# Output_dig2.net
KiCad netlist of a schematic drawn in Altium Designer
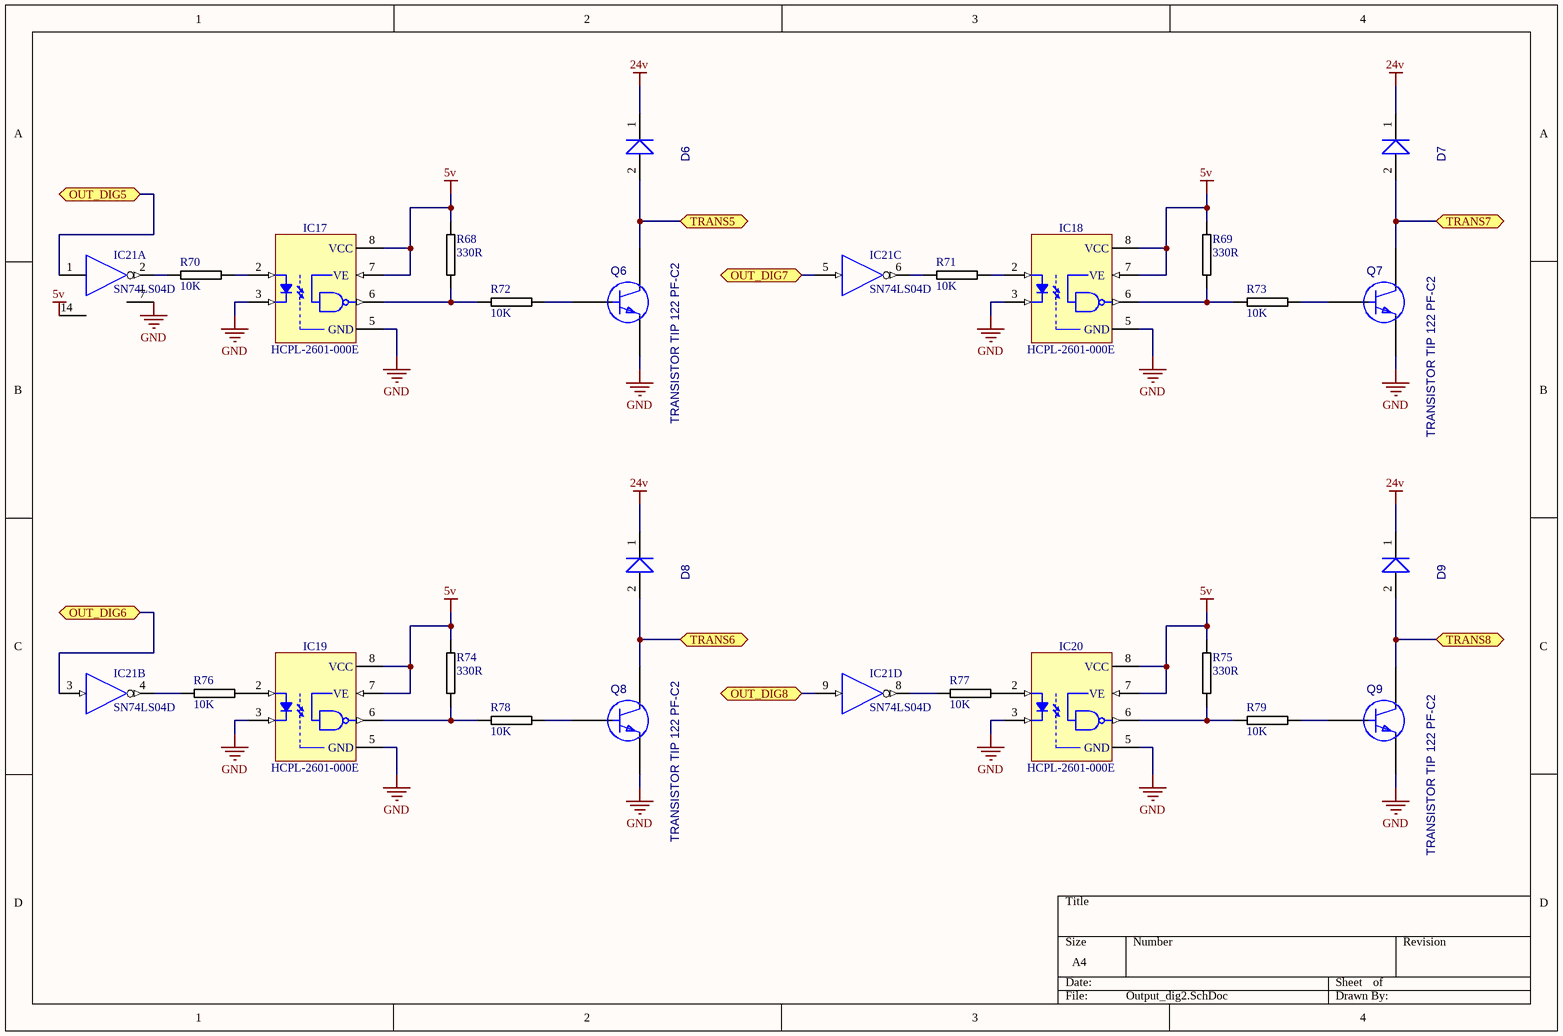
[diagram p0: Output_dig2.SchDoc]

(export (version "E")
  (design (tool "Eeschema 10.0.6"))
  (components
    (comp (ref "D6")
      (value "DIODO 1N4007 PF-B1")
      (footprint "DIODO DO41 PF-B1")
      (libsource (lib "GNATUS_COMPONENTES_BASE") (part "DIODO 1N4007 PF-B1"))
    )
    (comp (ref "D7")
      (value "DIODO 1N4007 PF-B1")
      (footprint "DIODO DO41 PF-B1")
      (libsource (lib "GNATUS_COMPONENTES_BASE") (part "DIODO 1N4007 PF-B1"))
    )
    (comp (ref "D8")
      (value "DIODO 1N4007 PF-B1")
      (footprint "DIODO DO41 PF-B1")
      (libsource (lib "GNATUS_COMPONENTES_BASE") (part "DIODO 1N4007 PF-B1"))
    )
    (comp (ref "D9")
      (value "DIODO 1N4007 PF-B1")
      (footprint "DIODO DO41 PF-B1")
      (libsource (lib "GNATUS_COMPONENTES_BASE") (part "DIODO 1N4007 PF-B1"))
    )
    (comp (ref "IC17")
      (value "HCPL-2601-000E")
      (footprint "DIP8-300")
      (description "Single Optocoupler")
      (fields (field (name "MANUFACTURER") "AVAGO TECHNOLOGIES") (field (name "AUTHOR") "CERN DEM JLC"))
      (libsource (lib "ICs And Semiconductors") (part "Optocoupler Type8"))
    )
    (comp (ref "IC18")
      (value "HCPL-2601-000E")
      (footprint "DIP8-300")
      (description "Single Optocoupler")
      (fields (field (name "MANUFACTURER") "AVAGO TECHNOLOGIES") (field (name "AUTHOR") "CERN DEM JLC"))
      (libsource (lib "ICs And Semiconductors") (part "Optocoupler Type8"))
    )
    (comp (ref "IC19")
      (value "HCPL-2601-000E")
      (footprint "DIP8-300")
      (description "Single Optocoupler")
      (fields (field (name "MANUFACTURER") "AVAGO TECHNOLOGIES") (field (name "AUTHOR") "CERN DEM JLC"))
      (libsource (lib "ICs And Semiconductors") (part "Optocoupler Type8"))
    )
    (comp (ref "IC20")
      (value "HCPL-2601-000E")
      (footprint "DIP8-300")
      (description "Single Optocoupler")
      (fields (field (name "MANUFACTURER") "AVAGO TECHNOLOGIES") (field (name "AUTHOR") "CERN DEM JLC"))
      (libsource (lib "ICs And Semiconductors") (part "Optocoupler Type8"))
    )
    (comp (ref "IC21")
      (value "SN74LS04D")
      (footprint "SOIC127P600X175-14N")
      (description "Hex Inverter")
      (fields (field (name "MANUFACTURER") "TEXAS INSTRUMENTS") (field (name "AUTHOR") "CERN DEM JLC"))
      (libsource (lib "ICs And Semiconductors") (part "7404"))
    )
    (comp (ref "Q6")
      (value "TRANSISTOR TIP 122 PF-C2")
      (footprint "TRANSISTOR TO220 PF-C2")
      (libsource (lib "GNATUS_COMPONENTES_BASE") (part "TRANSISTOR TIP 122 PF-C2"))
    )
    (comp (ref "Q7")
      (value "TRANSISTOR TIP 122 PF-C2")
      (footprint "TRANSISTOR TO220 PF-C2")
      (libsource (lib "GNATUS_COMPONENTES_BASE") (part "TRANSISTOR TIP 122 PF-C2"))
    )
    (comp (ref "Q8")
      (value "TRANSISTOR TIP 122 PF-C2")
      (footprint "TRANSISTOR TO220 PF-C2")
      (libsource (lib "GNATUS_COMPONENTES_BASE") (part "TRANSISTOR TIP 122 PF-C2"))
    )
    (comp (ref "Q9")
      (value "TRANSISTOR TIP 122 PF-C2")
      (footprint "TRANSISTOR TO220 PF-C2")
      (libsource (lib "GNATUS_COMPONENTES_BASE") (part "TRANSISTOR TIP 122 PF-C2"))
    )
    (comp (ref "R68")
      (value "330R")
      (footprint "0805R-330")
      (description "RESISTOR 0805 1/4 WATT THIN FILM")
      (libsource (lib "vh_altium_library") (part "0805R-330"))
    )
    (comp (ref "R69")
      (value "330R")
      (footprint "0805R-330")
      (description "RESISTOR 0805 1/4 WATT THIN FILM")
      (libsource (lib "vh_altium_library") (part "0805R-330"))
    )
    (comp (ref "R70")
      (value "10K")
      (footprint "0805R-10K")
      (description "RESISTOR 0805 1/4 WATT THIN FILM")
      (libsource (lib "vh_altium_library") (part "0805R-10K"))
    )
    (comp (ref "R71")
      (value "10K")
      (footprint "0805R-10K")
      (description "RESISTOR 0805 1/4 WATT THIN FILM")
      (libsource (lib "vh_altium_library") (part "0805R-10K"))
    )
    (comp (ref "R72")
      (value "10K")
      (footprint "0805R-10K")
      (description "RESISTOR 0805 1/4 WATT THIN FILM")
      (libsource (lib "vh_altium_library") (part "0805R-10K"))
    )
    (comp (ref "R73")
      (value "10K")
      (footprint "0805R-10K")
      (description "RESISTOR 0805 1/4 WATT THIN FILM")
      (libsource (lib "vh_altium_library") (part "0805R-10K"))
    )
    (comp (ref "R74")
      (value "330R")
      (footprint "0805R-330")
      (description "RESISTOR 0805 1/4 WATT THIN FILM")
      (libsource (lib "vh_altium_library") (part "0805R-330"))
    )
    (comp (ref "R75")
      (value "330R")
      (footprint "0805R-330")
      (description "RESISTOR 0805 1/4 WATT THIN FILM")
      (libsource (lib "vh_altium_library") (part "0805R-330"))
    )
    (comp (ref "R76")
      (value "10K")
      (footprint "0805R-10K")
      (description "RESISTOR 0805 1/4 WATT THIN FILM")
      (libsource (lib "vh_altium_library") (part "0805R-10K"))
    )
    (comp (ref "R77")
      (value "10K")
      (footprint "0805R-10K")
      (description "RESISTOR 0805 1/4 WATT THIN FILM")
      (libsource (lib "vh_altium_library") (part "0805R-10K"))
    )
    (comp (ref "R78")
      (value "10K")
      (footprint "0805R-10K")
      (description "RESISTOR 0805 1/4 WATT THIN FILM")
      (libsource (lib "vh_altium_library") (part "0805R-10K"))
    )
    (comp (ref "R79")
      (value "10K")
      (footprint "0805R-10K")
      (description "RESISTOR 0805 1/4 WATT THIN FILM")
      (libsource (lib "vh_altium_library") (part "0805R-10K"))
    )
  )
  (nets
    (net (code "1") (name "/OUT_DIG5") (class "Default")
      (node (ref "IC21") (pin "1") (pinfunction "A_1") (pintype "passive"))
    )
    (net (code "2") (name "/OUT_DIG6") (class "Default")
      (node (ref "IC21") (pin "3") (pinfunction "A_3") (pintype "input"))
    )
    (net (code "3") (name "/OUT_DIG7") (class "Default")
      (node (ref "IC21") (pin "5") (pinfunction "A_5") (pintype "input"))
    )
    (net (code "4") (name "/OUT_DIG8") (class "Default")
      (node (ref "IC21") (pin "9") (pinfunction "A_9") (pintype "input"))
    )
    (net (code "5") (name "/TRANS5") (class "Default")
      (node (ref "D6") (pin "2") (pinfunction "A_2") (pintype "passive"))
      (node (ref "Q6") (pin "2") (pinfunction "C_2") (pintype "passive"))
    )
    (net (code "6") (name "/TRANS6") (class "Default")
      (node (ref "D8") (pin "2") (pinfunction "A_2") (pintype "passive"))
      (node (ref "Q8") (pin "2") (pinfunction "C_2") (pintype "passive"))
    )
    (net (code "7") (name "/TRANS7") (class "Default")
      (node (ref "D7") (pin "2") (pinfunction "A_2") (pintype "passive"))
      (node (ref "Q7") (pin "2") (pinfunction "C_2") (pintype "passive"))
    )
    (net (code "8") (name "/TRANS8") (class "Default")
      (node (ref "D9") (pin "2") (pinfunction "A_2") (pintype "passive"))
      (node (ref "Q9") (pin "2") (pinfunction "C_2") (pintype "passive"))
    )
    (net (code "9") (name "5v") (class "Default")
      (node (ref "IC17") (pin "7") (pinfunction "VE_7") (pintype "input"))
      (node (ref "IC17") (pin "8") (pinfunction "VCC_8") (pintype "power_in"))
      (node (ref "IC18") (pin "7") (pinfunction "VE_7") (pintype "input"))
      (node (ref "IC18") (pin "8") (pinfunction "VCC_8") (pintype "power_in"))
      (node (ref "IC19") (pin "7") (pinfunction "VE_7") (pintype "input"))
      (node (ref "IC19") (pin "8") (pinfunction "VCC_8") (pintype "power_in"))
      (node (ref "IC20") (pin "7") (pinfunction "VE_7") (pintype "input"))
      (node (ref "IC20") (pin "8") (pinfunction "VCC_8") (pintype "power_in"))
      (node (ref "IC21") (pin "14") (pinfunction "VCC_14") (pintype "power_in"))
      (node (ref "R68") (pin "1") (pintype "passive"))
      (node (ref "R69") (pin "1") (pintype "passive"))
      (node (ref "R74") (pin "1") (pintype "passive"))
      (node (ref "R75") (pin "1") (pintype "passive"))
    )
    (net (code "10") (name "24v") (class "Default")
      (node (ref "D6") (pin "1") (pinfunction "K_1") (pintype "passive"))
      (node (ref "D7") (pin "1") (pinfunction "K_1") (pintype "passive"))
      (node (ref "D8") (pin "1") (pinfunction "K_1") (pintype "passive"))
      (node (ref "D9") (pin "1") (pinfunction "K_1") (pintype "passive"))
    )
    (net (code "11") (name "GND") (class "Default")
      (node (ref "IC17") (pin "3") (pinfunction "K_3") (pintype "input"))
      (node (ref "IC17") (pin "5") (pinfunction "GND_5") (pintype "power_in"))
      (node (ref "IC18") (pin "3") (pinfunction "K_3") (pintype "input"))
      (node (ref "IC18") (pin "5") (pinfunction "GND_5") (pintype "power_in"))
      (node (ref "IC19") (pin "3") (pinfunction "K_3") (pintype "input"))
      (node (ref "IC19") (pin "5") (pinfunction "GND_5") (pintype "power_in"))
      (node (ref "IC20") (pin "3") (pinfunction "K_3") (pintype "input"))
      (node (ref "IC20") (pin "5") (pinfunction "GND_5") (pintype "power_in"))
      (node (ref "IC21") (pin "7") (pinfunction "GND_7") (pintype "power_in"))
      (node (ref "Q6") (pin "3") (pinfunction "E_3") (pintype "passive"))
      (node (ref "Q7") (pin "3") (pinfunction "E_3") (pintype "passive"))
      (node (ref "Q8") (pin "3") (pinfunction "E_3") (pintype "passive"))
      (node (ref "Q9") (pin "3") (pinfunction "E_3") (pintype "passive"))
    )
    (net (code "12") (name "Net-(IC17-A)") (class "Default")
      (node (ref "IC17") (pin "2") (pinfunction "A_2") (pintype "input"))
      (node (ref "R70") (pin "2") (pintype "passive"))
    )
    (net (code "13") (name "Net-(IC17-VO)") (class "Default")
      (node (ref "IC17") (pin "6") (pinfunction "VO_6") (pintype "output"))
      (node (ref "R68") (pin "2") (pintype "passive"))
      (node (ref "R72") (pin "1") (pintype "passive"))
    )
    (net (code "14") (name "Net-(IC18-A)") (class "Default")
      (node (ref "IC18") (pin "2") (pinfunction "A_2") (pintype "input"))
      (node (ref "R71") (pin "2") (pintype "passive"))
    )
    (net (code "15") (name "Net-(IC18-VO)") (class "Default")
      (node (ref "IC18") (pin "6") (pinfunction "VO_6") (pintype "output"))
      (node (ref "R69") (pin "2") (pintype "passive"))
      (node (ref "R73") (pin "1") (pintype "passive"))
    )
    (net (code "16") (name "Net-(IC19-A)") (class "Default")
      (node (ref "IC19") (pin "2") (pinfunction "A_2") (pintype "input"))
      (node (ref "R76") (pin "2") (pintype "passive"))
    )
    (net (code "17") (name "Net-(IC19-VO)") (class "Default")
      (node (ref "IC19") (pin "6") (pinfunction "VO_6") (pintype "output"))
      (node (ref "R74") (pin "2") (pintype "passive"))
      (node (ref "R78") (pin "1") (pintype "passive"))
    )
    (net (code "18") (name "Net-(IC20-A)") (class "Default")
      (node (ref "IC20") (pin "2") (pinfunction "A_2") (pintype "input"))
      (node (ref "R77") (pin "2") (pintype "passive"))
    )
    (net (code "19") (name "Net-(IC20-VO)") (class "Default")
      (node (ref "IC20") (pin "6") (pinfunction "VO_6") (pintype "output"))
      (node (ref "R75") (pin "2") (pintype "passive"))
      (node (ref "R79") (pin "1") (pintype "passive"))
    )
    (net (code "20") (name "Net-(IC21A-~{O})") (class "Default")
      (node (ref "IC21") (pin "2") (pinfunction "~{O}_2") (pintype "output"))
      (node (ref "R70") (pin "1") (pintype "passive"))
    )
    (net (code "21") (name "Net-(IC21B-~{O})") (class "Default")
      (node (ref "IC21") (pin "4") (pinfunction "~{O}_4") (pintype "output"))
      (node (ref "R76") (pin "1") (pintype "passive"))
    )
    (net (code "22") (name "Net-(IC21C-~{O})") (class "Default")
      (node (ref "IC21") (pin "6") (pinfunction "~{O}_6") (pintype "output"))
      (node (ref "R71") (pin "1") (pintype "passive"))
    )
    (net (code "23") (name "Net-(IC21D-~{O})") (class "Default")
      (node (ref "IC21") (pin "8") (pinfunction "~{O}_8") (pintype "output"))
      (node (ref "R77") (pin "1") (pintype "passive"))
    )
    (net (code "24") (name "Net-(Q6-B)") (class "Default")
      (node (ref "Q6") (pin "1") (pinfunction "B_1") (pintype "passive"))
      (node (ref "R72") (pin "2") (pintype "passive"))
    )
    (net (code "25") (name "Net-(Q7-B)") (class "Default")
      (node (ref "Q7") (pin "1") (pinfunction "B_1") (pintype "passive"))
      (node (ref "R73") (pin "2") (pintype "passive"))
    )
    (net (code "26") (name "Net-(Q8-B)") (class "Default")
      (node (ref "Q8") (pin "1") (pinfunction "B_1") (pintype "passive"))
      (node (ref "R78") (pin "2") (pintype "passive"))
    )
    (net (code "27") (name "Net-(Q9-B)") (class "Default")
      (node (ref "Q9") (pin "1") (pinfunction "B_1") (pintype "passive"))
      (node (ref "R79") (pin "2") (pintype "passive"))
    )
    (net (code "28") (name "unconnected-(IC21B-GND-Pad7)") (class "Default")
      (node (ref "IC21") (pin "7") (pinfunction "GND_7") (pintype "power_in"))
    )
    (net (code "29") (name "unconnected-(IC21B-VCC-Pad14)") (class "Default")
      (node (ref "IC21") (pin "14") (pinfunction "VCC_14") (pintype "power_in"))
    )
    (net (code "30") (name "unconnected-(IC21C-GND-Pad7)") (class "Default")
      (node (ref "IC21") (pin "7") (pinfunction "GND_7") (pintype "power_in"))
    )
    (net (code "31") (name "unconnected-(IC21C-VCC-Pad14)") (class "Default")
      (node (ref "IC21") (pin "14") (pinfunction "VCC_14") (pintype "power_in"))
    )
    (net (code "32") (name "unconnected-(IC21D-GND-Pad7)") (class "Default")
      (node (ref "IC21") (pin "7") (pinfunction "GND_7") (pintype "power_in"))
    )
    (net (code "33") (name "unconnected-(IC21D-VCC-Pad14)") (class "Default")
      (node (ref "IC21") (pin "14") (pinfunction "VCC_14") (pintype "power_in"))
    )
  )
)
